# 05_HDMI_to_DP.net
KiCad netlist of a schematic drawn in Altium Designer
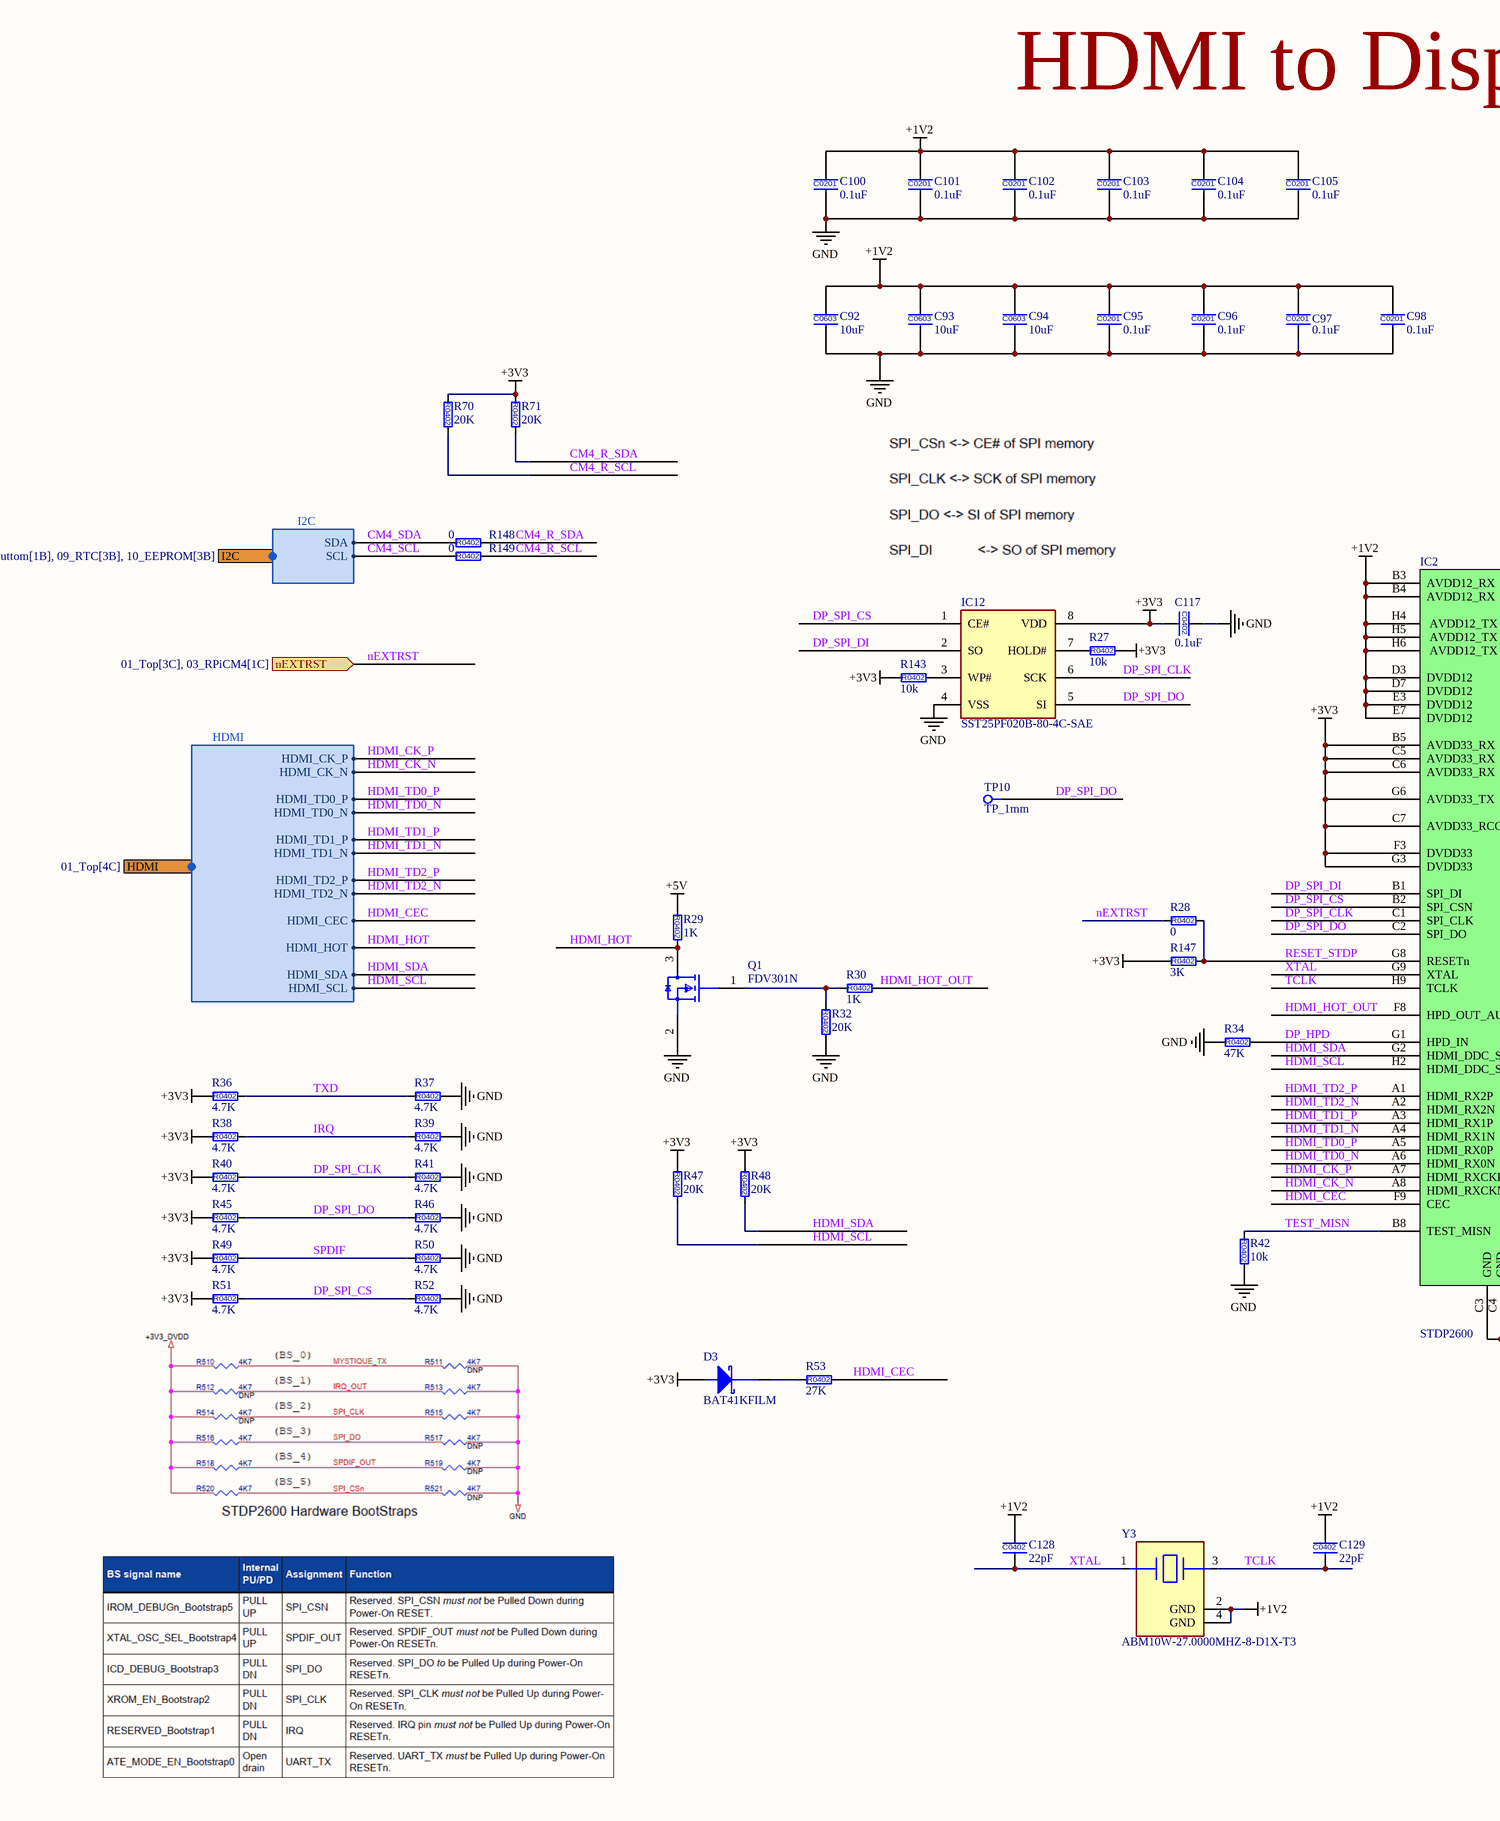
[diagram p0: 05_HDMI_to_DP.SchDoc, left]
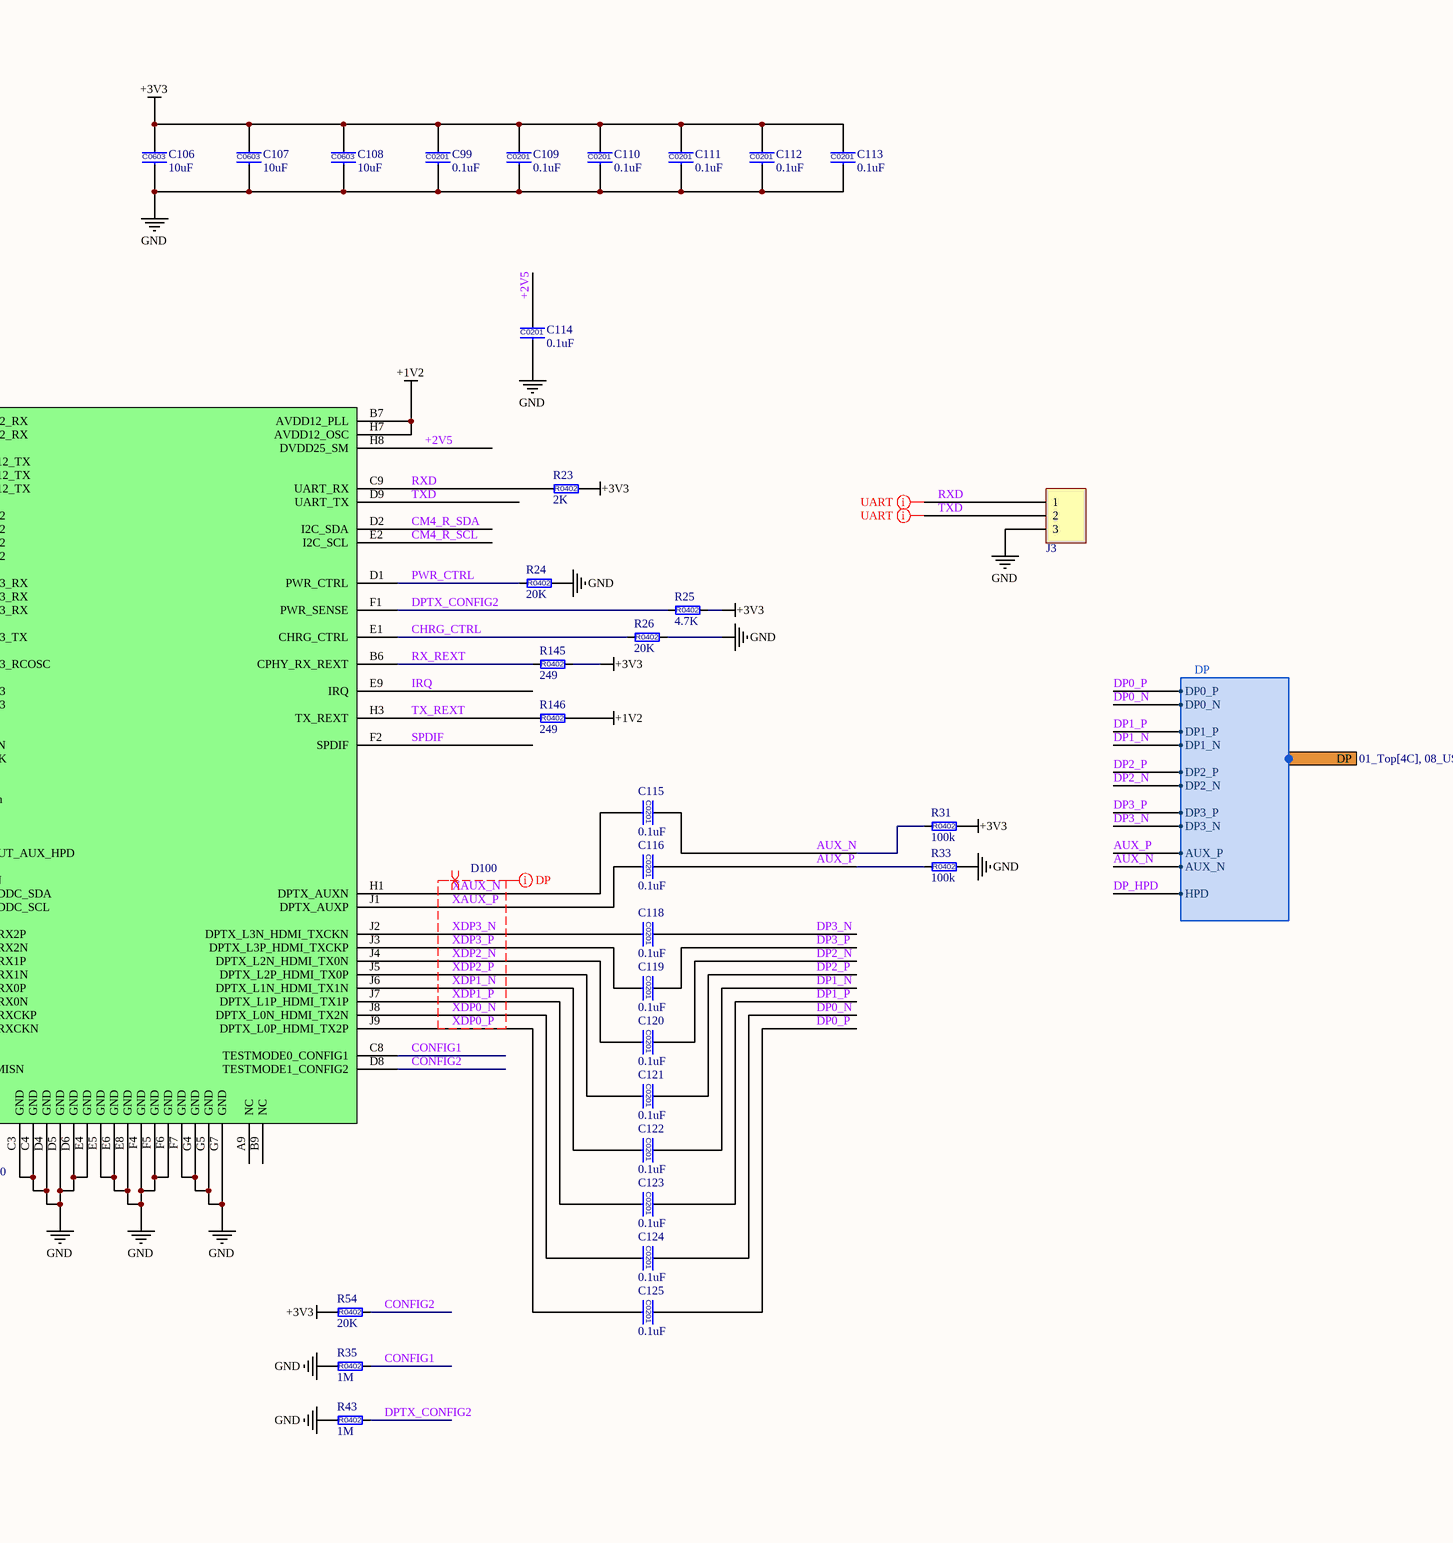
[diagram p1: 05_HDMI_to_DP.SchDoc, right]

(export (version "E")
  (design (tool "Eeschema 10.0.6"))
  (components
    (comp (ref "C92")
      (value "10uF")
      (footprint "C0603")
      (description "CAP CER 10uF 10% 10V X5R 0603")
      (fields
        (field (name "MANUFACTURER") "KYOCERA AVX")
        (field (name "MANUFACTURER PART NUMBER") "0603ZD106KAT2A")
      )
      (libsource (lib "Capacitor") (part "0603ZD106KAT2A"))
    )
    (comp (ref "C93")
      (value "10uF")
      (footprint "C0603")
      (description "CAP CER 10uF 10% 10V X5R 0603")
      (fields
        (field (name "MANUFACTURER") "KYOCERA AVX")
        (field (name "MANUFACTURER PART NUMBER") "0603ZD106KAT2A")
      )
      (libsource (lib "Capacitor") (part "0603ZD106KAT2A"))
    )
    (comp (ref "C94")
      (value "10uF")
      (footprint "C0603")
      (description "CAP CER 10uF 10% 10V X5R 0603")
      (fields
        (field (name "MANUFACTURER") "KYOCERA AVX")
        (field (name "MANUFACTURER PART NUMBER") "0603ZD106KAT2A")
      )
      (libsource (lib "Capacitor") (part "0603ZD106KAT2A"))
    )
    (comp (ref "C95")
      (value "0.1uF")
      (footprint "C0201")
      (description "CAP CER  0.1uF 10% 6.3V X5R 0201")
      (fields
        (field (name "MANUFACTURER") "AVX Corporation")
        (field (name "MANUFACTURER PART NUMBER") "02016D104KAT")
      )
      (libsource (lib "Capacitor") (part "02016D104KAT"))
    )
    (comp (ref "C96")
      (value "0.1uF")
      (footprint "C0201")
      (description "CAP CER  0.1uF 10% 6.3V X5R 0201")
      (fields
        (field (name "MANUFACTURER") "AVX Corporation")
        (field (name "MANUFACTURER PART NUMBER") "02016D104KAT")
      )
      (libsource (lib "Capacitor") (part "02016D104KAT"))
    )
    (comp (ref "C97")
      (value "0.1uF")
      (footprint "C0201")
      (description "CAP CER  0.1uF 10% 6.3V X5R 0201")
      (fields
        (field (name "MANUFACTURER") "AVX Corporation")
        (field (name "MANUFACTURER PART NUMBER") "02016D104KAT")
      )
      (libsource (lib "Capacitor") (part "02016D104KAT"))
    )
    (comp (ref "C98")
      (value "0.1uF")
      (footprint "C0201")
      (description "CAP CER  0.1uF 10% 6.3V X5R 0201")
      (fields
        (field (name "MANUFACTURER") "AVX Corporation")
        (field (name "MANUFACTURER PART NUMBER") "02016D104KAT")
      )
      (libsource (lib "Capacitor") (part "02016D104KAT"))
    )
    (comp (ref "C99")
      (value "0.1uF")
      (footprint "C0201")
      (description "CAP CER  0.1uF 10% 6.3V X5R 0201")
      (fields
        (field (name "MANUFACTURER") "AVX Corporation")
        (field (name "MANUFACTURER PART NUMBER") "02016D104KAT")
      )
      (libsource (lib "Capacitor") (part "02016D104KAT"))
    )
    (comp (ref "C100")
      (value "0.1uF")
      (footprint "C0201")
      (description "CAP CER  0.1uF 10% 6.3V X5R 0201")
      (fields
        (field (name "MANUFACTURER") "AVX Corporation")
        (field (name "MANUFACTURER PART NUMBER") "02016D104KAT")
      )
      (libsource (lib "Capacitor") (part "02016D104KAT"))
    )
    (comp (ref "C101")
      (value "0.1uF")
      (footprint "C0201")
      (description "CAP CER  0.1uF 10% 6.3V X5R 0201")
      (fields
        (field (name "MANUFACTURER") "AVX Corporation")
        (field (name "MANUFACTURER PART NUMBER") "02016D104KAT")
      )
      (libsource (lib "Capacitor") (part "02016D104KAT"))
    )
    (comp (ref "C102")
      (value "0.1uF")
      (footprint "C0201")
      (description "CAP CER  0.1uF 10% 6.3V X5R 0201")
      (fields
        (field (name "MANUFACTURER") "AVX Corporation")
        (field (name "MANUFACTURER PART NUMBER") "02016D104KAT")
      )
      (libsource (lib "Capacitor") (part "02016D104KAT"))
    )
    (comp (ref "C103")
      (value "0.1uF")
      (footprint "C0201")
      (description "CAP CER  0.1uF 10% 6.3V X5R 0201")
      (fields
        (field (name "MANUFACTURER") "AVX Corporation")
        (field (name "MANUFACTURER PART NUMBER") "02016D104KAT")
      )
      (libsource (lib "Capacitor") (part "02016D104KAT"))
    )
    (comp (ref "C104")
      (value "0.1uF")
      (footprint "C0201")
      (description "CAP CER  0.1uF 10% 6.3V X5R 0201")
      (fields
        (field (name "MANUFACTURER") "AVX Corporation")
        (field (name "MANUFACTURER PART NUMBER") "02016D104KAT")
      )
      (libsource (lib "Capacitor") (part "02016D104KAT"))
    )
    (comp (ref "C105")
      (value "0.1uF")
      (footprint "C0201")
      (description "CAP CER  0.1uF 10% 6.3V X5R 0201")
      (fields
        (field (name "MANUFACTURER") "AVX Corporation")
        (field (name "MANUFACTURER PART NUMBER") "02016D104KAT")
      )
      (libsource (lib "Capacitor") (part "02016D104KAT"))
    )
    (comp (ref "C106")
      (value "10uF")
      (footprint "C0603")
      (description "CAP CER 10uF 10% 10V X5R 0603")
      (fields
        (field (name "MANUFACTURER") "KYOCERA AVX")
        (field (name "MANUFACTURER PART NUMBER") "0603ZD106KAT2A")
      )
      (libsource (lib "Capacitor") (part "0603ZD106KAT2A"))
    )
    (comp (ref "C107")
      (value "10uF")
      (footprint "C0603")
      (description "CAP CER 10uF 10% 10V X5R 0603")
      (fields
        (field (name "MANUFACTURER") "KYOCERA AVX")
        (field (name "MANUFACTURER PART NUMBER") "0603ZD106KAT2A")
      )
      (libsource (lib "Capacitor") (part "0603ZD106KAT2A"))
    )
    (comp (ref "C108")
      (value "10uF")
      (footprint "C0603")
      (description "CAP CER 10uF 10% 10V X5R 0603")
      (fields
        (field (name "MANUFACTURER") "KYOCERA AVX")
        (field (name "MANUFACTURER PART NUMBER") "0603ZD106KAT2A")
      )
      (libsource (lib "Capacitor") (part "0603ZD106KAT2A"))
    )
    (comp (ref "C109")
      (value "0.1uF")
      (footprint "C0201")
      (description "CAP CER  0.1uF 10% 6.3V X5R 0201")
      (fields
        (field (name "MANUFACTURER") "AVX Corporation")
        (field (name "MANUFACTURER PART NUMBER") "02016D104KAT")
      )
      (libsource (lib "Capacitor") (part "02016D104KAT"))
    )
    (comp (ref "C110")
      (value "0.1uF")
      (footprint "C0201")
      (description "CAP CER  0.1uF 10% 6.3V X5R 0201")
      (fields
        (field (name "MANUFACTURER") "AVX Corporation")
        (field (name "MANUFACTURER PART NUMBER") "02016D104KAT")
      )
      (libsource (lib "Capacitor") (part "02016D104KAT"))
    )
    (comp (ref "C111")
      (value "0.1uF")
      (footprint "C0201")
      (description "CAP CER  0.1uF 10% 6.3V X5R 0201")
      (fields
        (field (name "MANUFACTURER") "AVX Corporation")
        (field (name "MANUFACTURER PART NUMBER") "02016D104KAT")
      )
      (libsource (lib "Capacitor") (part "02016D104KAT"))
    )
    (comp (ref "C112")
      (value "0.1uF")
      (footprint "C0201")
      (description "CAP CER  0.1uF 10% 6.3V X5R 0201")
      (fields
        (field (name "MANUFACTURER") "AVX Corporation")
        (field (name "MANUFACTURER PART NUMBER") "02016D104KAT")
      )
      (libsource (lib "Capacitor") (part "02016D104KAT"))
    )
    (comp (ref "C113")
      (value "0.1uF")
      (footprint "C0201")
      (description "CAP CER  0.1uF 10% 6.3V X5R 0201")
      (fields
        (field (name "MANUFACTURER") "AVX Corporation")
        (field (name "MANUFACTURER PART NUMBER") "02016D104KAT")
      )
      (libsource (lib "Capacitor") (part "02016D104KAT"))
    )
    (comp (ref "C114")
      (value "0.1uF")
      (footprint "C0201")
      (description "CAP CER  0.1uF 10% 6.3V X5R 0201")
      (fields
        (field (name "MANUFACTURER") "AVX Corporation")
        (field (name "MANUFACTURER PART NUMBER") "02016D104KAT")
      )
      (libsource (lib "Capacitor") (part "02016D104KAT"))
    )
    (comp (ref "C115")
      (value "0.1uF")
      (footprint "C0201")
      (description "CAP CER  0.1uF 10% 6.3V X5R 0201")
      (fields
        (field (name "MANUFACTURER") "AVX Corporation")
        (field (name "MANUFACTURER PART NUMBER") "02016D104KAT")
      )
      (libsource (lib "Capacitor") (part "02016D104KAT"))
    )
    (comp (ref "C116")
      (value "0.1uF")
      (footprint "C0201")
      (description "CAP CER  0.1uF 10% 6.3V X5R 0201")
      (fields
        (field (name "MANUFACTURER") "AVX Corporation")
        (field (name "MANUFACTURER PART NUMBER") "02016D104KAT")
      )
      (libsource (lib "Capacitor") (part "02016D104KAT"))
    )
    (comp (ref "C117")
      (value "0.1uF")
      (footprint "C0402")
      (description "CAP CER  0.1uF 10% 25V X5R 0402")
      (fields
        (field (name "MANUFACTURER") "AVX Corporation")
        (field (name "MANUFACTURER PART NUMBER") "04023D104KAT2A")
      )
      (libsource (lib "Capacitor") (part "04023D104KAT2A"))
    )
    (comp (ref "C118")
      (value "0.1uF")
      (footprint "C0201")
      (description "CAP CER  0.1uF 10% 6.3V X5R 0201")
      (fields
        (field (name "MANUFACTURER") "AVX Corporation")
        (field (name "MANUFACTURER PART NUMBER") "02016D104KAT")
      )
      (libsource (lib "Capacitor") (part "02016D104KAT"))
    )
    (comp (ref "C119")
      (value "0.1uF")
      (footprint "C0201")
      (description "CAP CER  0.1uF 10% 6.3V X5R 0201")
      (fields
        (field (name "MANUFACTURER") "AVX Corporation")
        (field (name "MANUFACTURER PART NUMBER") "02016D104KAT")
      )
      (libsource (lib "Capacitor") (part "02016D104KAT"))
    )
    (comp (ref "C120")
      (value "0.1uF")
      (footprint "C0201")
      (description "CAP CER  0.1uF 10% 6.3V X5R 0201")
      (fields
        (field (name "MANUFACTURER") "AVX Corporation")
        (field (name "MANUFACTURER PART NUMBER") "02016D104KAT")
      )
      (libsource (lib "Capacitor") (part "02016D104KAT"))
    )
    (comp (ref "C121")
      (value "0.1uF")
      (footprint "C0201")
      (description "CAP CER  0.1uF 10% 6.3V X5R 0201")
      (fields
        (field (name "MANUFACTURER") "AVX Corporation")
        (field (name "MANUFACTURER PART NUMBER") "02016D104KAT")
      )
      (libsource (lib "Capacitor") (part "02016D104KAT"))
    )
    (comp (ref "C122")
      (value "0.1uF")
      (footprint "C0201")
      (description "CAP CER  0.1uF 10% 6.3V X5R 0201")
      (fields
        (field (name "MANUFACTURER") "AVX Corporation")
        (field (name "MANUFACTURER PART NUMBER") "02016D104KAT")
      )
      (libsource (lib "Capacitor") (part "02016D104KAT"))
    )
    (comp (ref "C123")
      (value "0.1uF")
      (footprint "C0201")
      (description "CAP CER  0.1uF 10% 6.3V X5R 0201")
      (fields
        (field (name "MANUFACTURER") "AVX Corporation")
        (field (name "MANUFACTURER PART NUMBER") "02016D104KAT")
      )
      (libsource (lib "Capacitor") (part "02016D104KAT"))
    )
    (comp (ref "C124")
      (value "0.1uF")
      (footprint "C0201")
      (description "CAP CER  0.1uF 10% 6.3V X5R 0201")
      (fields
        (field (name "MANUFACTURER") "AVX Corporation")
        (field (name "MANUFACTURER PART NUMBER") "02016D104KAT")
      )
      (libsource (lib "Capacitor") (part "02016D104KAT"))
    )
    (comp (ref "C125")
      (value "0.1uF")
      (footprint "C0201")
      (description "CAP CER  0.1uF 10% 6.3V X5R 0201")
      (fields
        (field (name "MANUFACTURER") "AVX Corporation")
        (field (name "MANUFACTURER PART NUMBER") "02016D104KAT")
      )
      (libsource (lib "Capacitor") (part "02016D104KAT"))
    )
    (comp (ref "C128")
      (value "22pF")
      (footprint "C0402")
      (description "CAP CER 22pF 10% 25V NP0 0402")
      (fields
        (field (name "MANUFACTURER") "KYOCERA AVX")
        (field (name "MANUFACTURER PART NUMBER") "04023A220KAT2A")
      )
      (libsource (lib "Capacitor") (part "04023A220KAT2A"))
    )
    (comp (ref "C129")
      (value "22pF")
      (footprint "C0402")
      (description "CAP CER 22pF 10% 25V NP0 0402")
      (fields
        (field (name "MANUFACTURER") "KYOCERA AVX")
        (field (name "MANUFACTURER PART NUMBER") "04023A220KAT2A")
      )
      (libsource (lib "Capacitor") (part "04023A220KAT2A"))
    )
    (comp (ref "D3")
      (value "BAT41KFILM")
      (footprint "BAT41KFILM_SOD-523-2")
      (description "DIODE SCHOTTKY 100V 200MA SOD523")
      (fields
        (field (name "OCTOPART") "https://octopart.com/bat41kfilm-stmicroelectronics-658186")
        (field (name "MANUFACTURER") "STMicroelectronics")
      )
      (libsource (lib "new") (part "BAT41KFILM"))
    )
    (comp (ref "IC2")
      (value "STDP2600")
      (footprint "STDP2600_BGA-81")
      (description "Advanced HDMI to DisplayPort converter")
      (fields (field (name "PART NUMBER") "IC0077") (field (name "MANUFACTURER") "Kinetic Technologies"))
      (libsource (lib "new") (part "STDP2600"))
    )
    (comp (ref "IC12")
      (value "SST25PF020B-80-4C-SAE")
      (footprint "SST25PF020B-80-4C-SAE_SOIC_8")
      (description "150 mils SOIC 2.3-3.6V 2 Mbit SPI Flash 8 SOIC 3.90mm(.150in) TUBE RoHS Compliant: Yes")
      (fields
        (field (name "MOUSER PART NUMBER") "579-020B-80-4C-SAE")
        (field (name "MANUFACTURER") "Microchip")
      )
      (libsource (lib "new") (part "SST25PF020B-80-4C-SAE"))
    )
    (comp (ref "J3")
      (value "PLS-3")
      (footprint "PLS-3-3D")
      (description "Board to Board Connector Straight Header Single Row 3 Position 2.54mm Pitch Through Hole Bag")
      (fields
        (field (name "MANUFACTURER") "Amphenol")
        (field (name "MANUFACTURER PART NUMBER") "G800W305018EU")
      )
      (libsource (lib "Connector") (part "PLS-3"))
    )
    (comp (ref "Q1")
      (value "FDV301N")
      (footprint "FDV301N_SOT_23")
      (description "MOSFET N-CH 25V 220MA SOT-23")
      (fields
        (field (name "MANUFACTURER") "ON Semiconductor")
        (field (name "OCTOPART") "https://octopart.com/fdv301n-on+semiconductor-84326713")
      )
      (libsource (lib "new") (part "FDV301N"))
    )
    (comp (ref "R23")
      (value "2K")
      (footprint "R0402")
      (description "RES SMD 2K ohm 1% 1/16W R0402")
      (fields
        (field (name "MANUFACTURER") "Vishay")
        (field (name "MANUFACTURER PART NUMBER") "CRCW04022K00FKEE")
      )
      (libsource (lib "Resistor") (part "CRCW04022K00FKEE"))
    )
    (comp (ref "R24")
      (value "20K")
      (footprint "R0402")
      (description "RES SMD 20K ohm 1% 1/16W R0402")
      (fields
        (field (name "MANUFACTURER") "Vishay Dale")
        (field (name "MANUFACTURER PART NUMBER") "CRCW040220K0FK")
      )
      (libsource (lib "Resistor") (part "CRCW040220K0FK"))
    )
    (comp (ref "R25")
      (value "4.7K")
      (footprint "R0402")
      (description "RES SMD 4.7K ohm 1% 1/16W R0402")
      (fields
        (field (name "MANUFACTURER") "Vishay Dale")
        (field (name "MANUFACTURER PART NUMBER") "CRCW04024K7FK")
      )
      (libsource (lib "Resistor") (part "CRCW04024K7FK"))
    )
    (comp (ref "R26")
      (value "20K")
      (footprint "R0402")
      (description "RES SMD 20K ohm 1% 1/16W R0402")
      (fields
        (field (name "MANUFACTURER") "Vishay Dale")
        (field (name "MANUFACTURER PART NUMBER") "CRCW040220K0FK")
      )
      (libsource (lib "Resistor") (part "CRCW040220K0FK"))
    )
    (comp (ref "R27")
      (value "10k")
      (footprint "R0402")
      (description "RES SMD 10K ohm 1% 1/16W R0402")
      (fields
        (field (name "MANUFACTURER") "Vishay Dale")
        (field (name "MANUFACTURER PART NUMBER") "CRCW040210K0FK")
      )
      (libsource (lib "Resistor") (part "CRCW040210K0FK"))
    )
    (comp (ref "R28")
      (value "0")
      (footprint "R0402")
      (description "RES SMD 0 ohm 1/16W R0402")
      (fields
        (field (name "MANUFACTURER") "Vishay Dale")
        (field (name "MANUFACTURER PART NUMBER") "CRCW04020000Z0")
      )
      (libsource (lib "Resistor") (part "CRCW04020000Z0"))
    )
    (comp (ref "R29")
      (value "1K")
      (footprint "R0402")
      (description "RES SMD 1K ohm 1% 1/16W R0402")
      (fields
        (field (name "MANUFACTURER") "Vishay Dale")
        (field (name "MANUFACTURER PART NUMBER") "CRCW04021K00FK")
      )
      (libsource (lib "Resistor") (part "CRCW04021K00FK"))
    )
    (comp (ref "R30")
      (value "1K")
      (footprint "R0402")
      (description "RES SMD 1K ohm 1% 1/16W R0402")
      (fields
        (field (name "MANUFACTURER") "Vishay Dale")
        (field (name "MANUFACTURER PART NUMBER") "CRCW04021K00FK")
      )
      (libsource (lib "Resistor") (part "CRCW04021K00FK"))
    )
    (comp (ref "R31")
      (value "100k")
      (footprint "R0402")
      (description "RES SMD 100K ohm 1% 1/16W R0402")
      (fields
        (field (name "MANUFACTURER") "Vishay Dale")
        (field (name "MANUFACTURER PART NUMBER") "CRCW0402100KFK")
      )
      (libsource (lib "Resistor") (part "CRCW0402100KFK"))
    )
    (comp (ref "R32")
      (value "20K")
      (footprint "R0402")
      (description "RES SMD 20K ohm 1% 1/16W R0402")
      (fields
        (field (name "MANUFACTURER") "Vishay Dale")
        (field (name "MANUFACTURER PART NUMBER") "CRCW040220K0FK")
      )
      (libsource (lib "Resistor") (part "CRCW040220K0FK"))
    )
    (comp (ref "R33")
      (value "100k")
      (footprint "R0402")
      (description "RES SMD 100K ohm 1% 1/16W R0402")
      (fields
        (field (name "MANUFACTURER") "Vishay Dale")
        (field (name "MANUFACTURER PART NUMBER") "CRCW0402100KFK")
      )
      (libsource (lib "Resistor") (part "CRCW0402100KFK"))
    )
    (comp (ref "R34")
      (value "47K")
      (footprint "R0402")
      (description "RES SMD 47K ohm 1% 1/16W R0402")
      (fields
        (field (name "MANUFACTURER") "Vishay Dale")
        (field (name "MANUFACTURER PART NUMBER") "CRCW040247K0FK")
      )
      (libsource (lib "Resistor") (part "CRCW040247K0FK"))
    )
    (comp (ref "R35")
      (value "1M")
      (footprint "R0402")
      (description "RES SMD 1M ohm 1% 1/16W R0402")
      (fields
        (field (name "MANUFACTURER") "Vishay")
        (field (name "MANUFACTURER PART NUMBER") "CRCW04021M00FKEDC")
      )
      (libsource (lib "Resistor") (part "CRCW04021M00FKEDC"))
    )
    (comp (ref "R36")
      (value "4.7K")
      (footprint "R0402")
      (description "RES SMD 4.7K ohm 1% 1/16W R0402")
      (fields
        (field (name "MANUFACTURER") "Vishay Dale")
        (field (name "MANUFACTURER PART NUMBER") "CRCW04024K7FK")
      )
      (libsource (lib "Resistor") (part "CRCW04024K7FK"))
    )
    (comp (ref "R37")
      (value "4.7K")
      (footprint "R0402")
      (description "RES SMD 4.7K ohm 1% 1/16W R0402")
      (fields
        (field (name "MANUFACTURER") "Vishay Dale")
        (field (name "MANUFACTURER PART NUMBER") "CRCW04024K7FK")
      )
      (libsource (lib "Resistor") (part "CRCW04024K7FK"))
    )
    (comp (ref "R38")
      (value "4.7K")
      (footprint "R0402")
      (description "RES SMD 4.7K ohm 1% 1/16W R0402")
      (fields
        (field (name "MANUFACTURER") "Vishay Dale")
        (field (name "MANUFACTURER PART NUMBER") "CRCW04024K7FK")
      )
      (libsource (lib "Resistor") (part "CRCW04024K7FK"))
    )
    (comp (ref "R39")
      (value "4.7K")
      (footprint "R0402")
      (description "RES SMD 4.7K ohm 1% 1/16W R0402")
      (fields
        (field (name "MANUFACTURER") "Vishay Dale")
        (field (name "MANUFACTURER PART NUMBER") "CRCW04024K7FK")
      )
      (libsource (lib "Resistor") (part "CRCW04024K7FK"))
    )
    (comp (ref "R40")
      (value "4.7K")
      (footprint "R0402")
      (description "RES SMD 4.7K ohm 1% 1/16W R0402")
      (fields
        (field (name "MANUFACTURER") "Vishay Dale")
        (field (name "MANUFACTURER PART NUMBER") "CRCW04024K7FK")
      )
      (libsource (lib "Resistor") (part "CRCW04024K7FK"))
    )
    (comp (ref "R41")
      (value "4.7K")
      (footprint "R0402")
      (description "RES SMD 4.7K ohm 1% 1/16W R0402")
      (fields
        (field (name "MANUFACTURER") "Vishay Dale")
        (field (name "MANUFACTURER PART NUMBER") "CRCW04024K7FK")
      )
      (libsource (lib "Resistor") (part "CRCW04024K7FK"))
    )
    (comp (ref "R42")
      (value "10k")
      (footprint "R0402")
      (description "RES SMD 10K ohm 1% 1/16W R0402")
      (fields
        (field (name "MANUFACTURER") "Vishay Dale")
        (field (name "MANUFACTURER PART NUMBER") "CRCW040210K0FK")
      )
      (libsource (lib "Resistor") (part "CRCW040210K0FK"))
    )
    (comp (ref "R43")
      (value "1M")
      (footprint "R0402")
      (description "RES SMD 1M ohm 1% 1/16W R0402")
      (fields
        (field (name "MANUFACTURER") "Vishay")
        (field (name "MANUFACTURER PART NUMBER") "CRCW04021M00FKEDC")
      )
      (libsource (lib "Resistor") (part "CRCW04021M00FKEDC"))
    )
    (comp (ref "R45")
      (value "4.7K")
      (footprint "R0402")
      (description "RES SMD 4.7K ohm 1% 1/16W R0402")
      (fields
        (field (name "MANUFACTURER") "Vishay Dale")
        (field (name "MANUFACTURER PART NUMBER") "CRCW04024K7FK")
      )
      (libsource (lib "Resistor") (part "CRCW04024K7FK"))
    )
    (comp (ref "R46")
      (value "4.7K")
      (footprint "R0402")
      (description "RES SMD 4.7K ohm 1% 1/16W R0402")
      (fields
        (field (name "MANUFACTURER") "Vishay Dale")
        (field (name "MANUFACTURER PART NUMBER") "CRCW04024K7FK")
      )
      (libsource (lib "Resistor") (part "CRCW04024K7FK"))
    )
    (comp (ref "R47")
      (value "20K")
      (footprint "R0402")
      (description "RES SMD 20K ohm 1% 1/16W R0402")
      (fields
        (field (name "MANUFACTURER") "Vishay Dale")
        (field (name "MANUFACTURER PART NUMBER") "CRCW040220K0FK")
      )
      (libsource (lib "Resistor") (part "CRCW040220K0FK"))
    )
    (comp (ref "R48")
      (value "20K")
      (footprint "R0402")
      (description "RES SMD 20K ohm 1% 1/16W R0402")
      (fields
        (field (name "MANUFACTURER") "Vishay Dale")
        (field (name "MANUFACTURER PART NUMBER") "CRCW040220K0FK")
      )
      (libsource (lib "Resistor") (part "CRCW040220K0FK"))
    )
    (comp (ref "R49")
      (value "4.7K")
      (footprint "R0402")
      (description "RES SMD 4.7K ohm 1% 1/16W R0402")
      (fields
        (field (name "MANUFACTURER") "Vishay Dale")
        (field (name "MANUFACTURER PART NUMBER") "CRCW04024K7FK")
      )
      (libsource (lib "Resistor") (part "CRCW04024K7FK"))
    )
    (comp (ref "R50")
      (value "4.7K")
      (footprint "R0402")
      (description "RES SMD 4.7K ohm 1% 1/16W R0402")
      (fields
        (field (name "MANUFACTURER") "Vishay Dale")
        (field (name "MANUFACTURER PART NUMBER") "CRCW04024K7FK")
      )
      (libsource (lib "Resistor") (part "CRCW04024K7FK"))
    )
    (comp (ref "R51")
      (value "4.7K")
      (footprint "R0402")
      (description "RES SMD 4.7K ohm 1% 1/16W R0402")
      (fields
        (field (name "MANUFACTURER") "Vishay Dale")
        (field (name "MANUFACTURER PART NUMBER") "CRCW04024K7FK")
      )
      (libsource (lib "Resistor") (part "CRCW04024K7FK"))
    )
    (comp (ref "R52")
      (value "4.7K")
      (footprint "R0402")
      (description "RES SMD 4.7K ohm 1% 1/16W R0402")
      (fields
        (field (name "MANUFACTURER") "Vishay Dale")
        (field (name "MANUFACTURER PART NUMBER") "CRCW04024K7FK")
      )
      (libsource (lib "Resistor") (part "CRCW04024K7FK"))
    )
    (comp (ref "R53")
      (value "27K")
      (footprint "R0402")
      (description "RES SMD 27K ohm 1% 1/16W R0402")
      (fields
        (field (name "MANUFACTURER") "Vishay Dale")
        (field (name "MANUFACTURER PART NUMBER") "CRCW040227K0FK")
      )
      (libsource (lib "Resistor") (part "CRCW040227K0FK"))
    )
    (comp (ref "R54")
      (value "20K")
      (footprint "R0402")
      (description "RES SMD 20K ohm 1% 1/16W R0402")
      (fields
        (field (name "MANUFACTURER") "Vishay Dale")
        (field (name "MANUFACTURER PART NUMBER") "CRCW040220K0FK")
      )
      (libsource (lib "Resistor") (part "CRCW040220K0FK"))
    )
    (comp (ref "R70")
      (value "20K")
      (footprint "R0402")
      (description "RES SMD 20K ohm 1% 1/16W R0402")
      (fields
        (field (name "MANUFACTURER") "Vishay Dale")
        (field (name "MANUFACTURER PART NUMBER") "CRCW040220K0FK")
      )
      (libsource (lib "Resistor") (part "CRCW040220K0FK"))
    )
    (comp (ref "R71")
      (value "20K")
      (footprint "R0402")
      (description "RES SMD 20K ohm 1% 1/16W R0402")
      (fields
        (field (name "MANUFACTURER") "Vishay Dale")
        (field (name "MANUFACTURER PART NUMBER") "CRCW040220K0FK")
      )
      (libsource (lib "Resistor") (part "CRCW040220K0FK"))
    )
    (comp (ref "R143")
      (value "10k")
      (footprint "R0402")
      (description "RES SMD 10K ohm 1% 1/16W R0402")
      (fields
        (field (name "MANUFACTURER") "Vishay Dale")
        (field (name "MANUFACTURER PART NUMBER") "CRCW040210K0FK")
      )
      (libsource (lib "Resistor") (part "CRCW040210K0FK"))
    )
    (comp (ref "R145")
      (value "249")
      (footprint "R0402")
      (description "RES SMD 249 ohm 1% 1/16W R0402")
      (fields
        (field (name "MANUFACTURER") "Vishay")
        (field (name "MANUFACTURER PART NUMBER") "CRCW0402249RFKEDC")
      )
      (libsource (lib "Resistor") (part "CRCW0402249RFKEDC"))
    )
    (comp (ref "R146")
      (value "249")
      (footprint "R0402")
      (description "RES SMD 249 ohm 1% 1/16W R0402")
      (fields
        (field (name "MANUFACTURER") "Vishay")
        (field (name "MANUFACTURER PART NUMBER") "CRCW0402249RFKEDC")
      )
      (libsource (lib "Resistor") (part "CRCW0402249RFKEDC"))
    )
    (comp (ref "R147")
      (value "3K")
      (footprint "R0402")
      (description "RES SMD 3K ohm 1% 1/16W R0402")
      (fields
        (field (name "MANUFACTURER") "Vishay")
        (field (name "MANUFACTURER PART NUMBER") "CRCW04023K00FKED")
      )
      (libsource (lib "Resistor") (part "CRCW04023K00FKED"))
    )
    (comp (ref "R148")
      (value "0")
      (footprint "R0402")
      (description "RES SMD 0 ohm 1/16W R0402")
      (fields
        (field (name "MANUFACTURER") "Vishay Dale")
        (field (name "MANUFACTURER PART NUMBER") "CRCW04020000Z0")
      )
      (libsource (lib "Resistor") (part "CRCW04020000Z0"))
    )
    (comp (ref "R149")
      (value "0")
      (footprint "R0402")
      (description "RES SMD 0 ohm 1/16W R0402")
      (fields
        (field (name "MANUFACTURER") "Vishay Dale")
        (field (name "MANUFACTURER PART NUMBER") "CRCW04020000Z0")
      )
      (libsource (lib "Resistor") (part "CRCW04020000Z0"))
    )
    (comp (ref "TP10")
      (value "TP_1mm")
      (footprint "TP_1MM")
      (description "Testpoint 1mm")
      (fields (field (name "MANUFACTURER PART NUMBER") "General Test Point"))
      (libsource (lib "test_point_solder_bridge") (part "TP_1mm"))
    )
    (comp (ref "Y3")
      (value "ABM10W-27.0000MHZ-8-D1X-T3")
      (footprint "ABM10W")
      (description "CRYSTAL 27.0000MHZ 8PF SMD, 2.5x2mm, RoHS")
      (fields (field (name "MANUFACTURER") "Abracon"))
      (libsource (lib "new") (part "ABM10W-27.0000MHZ-8-D1X-T3"))
    )
  )
  (nets
    (net (code "4") (name "+1V2") (class "Default")
      (node (ref "C100") (pin "1") (pinfunction "1_1") (pintype "passive"))
      (node (ref "C101") (pin "1") (pinfunction "1_1") (pintype "passive"))
      (node (ref "C102") (pin "1") (pinfunction "1_1") (pintype "passive"))
      (node (ref "C103") (pin "1") (pinfunction "1_1") (pintype "passive"))
      (node (ref "C104") (pin "1") (pinfunction "1_1") (pintype "passive"))
      (node (ref "C105") (pin "1") (pinfunction "1_1") (pintype "passive"))
      (node (ref "C128") (pin "1") (pinfunction "1_1") (pintype "passive"))
      (node (ref "C129") (pin "1") (pinfunction "1_1") (pintype "passive"))
      (node (ref "C92") (pin "1") (pinfunction "1_1") (pintype "passive"))
      (node (ref "C93") (pin "1") (pinfunction "1_1") (pintype "passive"))
      (node (ref "C94") (pin "1") (pinfunction "1_1") (pintype "passive"))
      (node (ref "C95") (pin "1") (pinfunction "1_1") (pintype "passive"))
      (node (ref "C96") (pin "1") (pinfunction "1_1") (pintype "passive"))
      (node (ref "C97") (pin "1") (pinfunction "1_1") (pintype "passive"))
      (node (ref "C98") (pin "1") (pinfunction "1_1") (pintype "passive"))
      (node (ref "IC2") (pin "B3") (pinfunction "AVDD12_RX_B3") (pintype "passive"))
      (node (ref "IC2") (pin "B4") (pinfunction "AVDD12_RX_B4") (pintype "passive"))
      (node (ref "IC2") (pin "B7") (pinfunction "AVDD12_PLL_B7") (pintype "passive"))
      (node (ref "IC2") (pin "D3") (pinfunction "DVDD12_D3") (pintype "passive"))
      (node (ref "IC2") (pin "D7") (pinfunction "DVDD12_D7") (pintype "passive"))
      (node (ref "IC2") (pin "E3") (pinfunction "DVDD12_E3") (pintype "passive"))
      (node (ref "IC2") (pin "E7") (pinfunction "DVDD12_E7") (pintype "passive"))
      (node (ref "IC2") (pin "H4") (pinfunction "_AVDD12_TX_H4") (pintype "passive"))
      (node (ref "IC2") (pin "H5") (pinfunction "_AVDD12_TX_H5") (pintype "passive"))
      (node (ref "IC2") (pin "H6") (pinfunction "_AVDD12_TX_H6") (pintype "passive"))
      (node (ref "IC2") (pin "H7") (pinfunction "AVDD12_OSC_H7") (pintype "passive"))
      (node (ref "R146") (pin "2") (pinfunction "2_2") (pintype "passive"))
      (node (ref "Y3") (pin "2") (pinfunction "GND_2") (pintype "power_in"))
      (node (ref "Y3") (pin "4") (pinfunction "GND_4") (pintype "power_in"))
    )
    (net (code "5") (name "+3V3") (class "Default")
      (node (ref "C106") (pin "1") (pinfunction "1_1") (pintype "passive"))
      (node (ref "C107") (pin "1") (pinfunction "1_1") (pintype "passive"))
      (node (ref "C108") (pin "1") (pinfunction "1_1") (pintype "passive"))
      (node (ref "C109") (pin "1") (pinfunction "1_1") (pintype "passive"))
      (node (ref "C110") (pin "1") (pinfunction "1_1") (pintype "passive"))
      (node (ref "C111") (pin "1") (pinfunction "1_1") (pintype "passive"))
      (node (ref "C112") (pin "1") (pinfunction "1_1") (pintype "passive"))
      (node (ref "C113") (pin "1") (pinfunction "1_1") (pintype "passive"))
      (node (ref "C117") (pin "2") (pinfunction "2_2") (pintype "passive"))
      (node (ref "C99") (pin "1") (pinfunction "1_1") (pintype "passive"))
      (node (ref "D3") (pin "2") (pinfunction "Anode_2") (pintype "passive"))
      (node (ref "IC12") (pin "8") (pinfunction "VDD_8") (pintype "passive"))
      (node (ref "IC2") (pin "B5") (pinfunction "AVDD33_RX_B5") (pintype "passive"))
      (node (ref "IC2") (pin "C5") (pinfunction "AVDD33_RX_C5") (pintype "passive"))
      (node (ref "IC2") (pin "C6") (pinfunction "AVDD33_RX_C6") (pintype "passive"))
      (node (ref "IC2") (pin "C7") (pinfunction "AVDD33_RCOSC_C7") (pintype "passive"))
      (node (ref "IC2") (pin "F3") (pinfunction "DVDD33_F3") (pintype "passive"))
      (node (ref "IC2") (pin "G3") (pinfunction "DVDD33_G3") (pintype "passive"))
      (node (ref "IC2") (pin "G6") (pinfunction "AVDD33_TX_G6") (pintype "passive"))
      (node (ref "R143") (pin "1") (pinfunction "1_1") (pintype "passive"))
      (node (ref "R145") (pin "2") (pinfunction "2_2") (pintype "passive"))
      (node (ref "R147") (pin "1") (pinfunction "1_1") (pintype "passive"))
      (node (ref "R23") (pin "2") (pinfunction "2_2") (pintype "passive"))
      (node (ref "R25") (pin "2") (pinfunction "2_2") (pintype "passive"))
      (node (ref "R27") (pin "2") (pinfunction "2_2") (pintype "passive"))
      (node (ref "R31") (pin "2") (pinfunction "2_2") (pintype "passive"))
      (node (ref "R36") (pin "1") (pinfunction "1_1") (pintype "passive"))
      (node (ref "R38") (pin "1") (pinfunction "1_1") (pintype "passive"))
      (node (ref "R40") (pin "1") (pinfunction "1_1") (pintype "passive"))
      (node (ref "R45") (pin "1") (pinfunction "1_1") (pintype "passive"))
      (node (ref "R47") (pin "1") (pinfunction "1_1") (pintype "passive"))
      (node (ref "R48") (pin "1") (pinfunction "1_1") (pintype "passive"))
      (node (ref "R49") (pin "1") (pinfunction "1_1") (pintype "passive"))
      (node (ref "R51") (pin "1") (pinfunction "1_1") (pintype "passive"))
      (node (ref "R54") (pin "1") (pinfunction "1_1") (pintype "passive"))
      (node (ref "R70") (pin "1") (pinfunction "1_1") (pintype "passive"))
      (node (ref "R71") (pin "1") (pinfunction "1_1") (pintype "passive"))
    )
    (net (code "6") (name "+5V") (class "Default")
      (node (ref "R29") (pin "1") (pinfunction "1_1") (pintype "passive"))
    )
    (net (code "7") (name "/+2V5") (class "Default")
      (node (ref "C114") (pin "1") (pinfunction "1_1") (pintype "passive"))
      (node (ref "IC2") (pin "H8") (pinfunction "DVDD25_SM_H8") (pintype "passive"))
    )
    (net (code "8") (name "/AUX_N") (class "Default")
      (node (ref "C115") (pin "1") (pinfunction "1_1") (pintype "passive"))
      (node (ref "R31") (pin "1") (pinfunction "1_1") (pintype "passive"))
    )
    (net (code "9") (name "/AUX_P") (class "Default")
      (node (ref "C116") (pin "1") (pinfunction "1_1") (pintype "passive"))
      (node (ref "R33") (pin "1") (pinfunction "1_1") (pintype "passive"))
    )
    (net (code "10") (name "/CHRG_CTRL") (class "Default")
      (node (ref "IC2") (pin "E1") (pinfunction "CHRG_CTRL_E1") (pintype "passive"))
      (node (ref "R26") (pin "1") (pinfunction "1_1") (pintype "passive"))
    )
    (net (code "11") (name "/CM4_R_SCL") (class "Default")
      (node (ref "IC2") (pin "E2") (pinfunction "I2C_SCL_E2") (pintype "passive"))
      (node (ref "R149") (pin "2") (pinfunction "2_2") (pintype "passive"))
      (node (ref "R70") (pin "2") (pinfunction "2_2") (pintype "passive"))
    )
    (net (code "12") (name "/CM4_R_SDA") (class "Default")
      (node (ref "IC2") (pin "D2") (pinfunction "I2C_SDA_D2") (pintype "passive"))
      (node (ref "R148") (pin "2") (pinfunction "2_2") (pintype "passive"))
      (node (ref "R71") (pin "2") (pinfunction "2_2") (pintype "passive"))
    )
    (net (code "13") (name "/CM4_SCL") (class "Default")
      (node (ref "R149") (pin "1") (pinfunction "1_1") (pintype "passive"))
    )
    (net (code "14") (name "/CM4_SDA") (class "Default")
      (node (ref "R148") (pin "1") (pinfunction "1_1") (pintype "passive"))
    )
    (net (code "15") (name "/CONFIG1") (class "Default")
      (node (ref "IC2") (pin "C8") (pinfunction "TESTMODE0_CONFIG1_C8") (pintype "passive"))
      (node (ref "R35") (pin "2") (pinfunction "2_2") (pintype "passive"))
    )
    (net (code "16") (name "/CONFIG2") (class "Default")
      (node (ref "IC2") (pin "D8") (pinfunction "TESTMODE1_CONFIG2_D8") (pintype "passive"))
      (node (ref "R54") (pin "2") (pinfunction "2_2") (pintype "passive"))
    )
    (net (code "17") (name "/DP0_N") (class "Default")
      (node (ref "C124") (pin "1") (pinfunction "1_1") (pintype "passive"))
    )
    (net (code "18") (name "/DP0_P") (class "Default")
      (node (ref "C125") (pin "1") (pinfunction "1_1") (pintype "passive"))
    )
    (net (code "19") (name "/DP1_N") (class "Default")
      (node (ref "C122") (pin "1") (pinfunction "1_1") (pintype "passive"))
    )
    (net (code "20") (name "/DP1_P") (class "Default")
      (node (ref "C123") (pin "1") (pinfunction "1_1") (pintype "passive"))
    )
    (net (code "21") (name "/DP2_N") (class "Default")
      (node (ref "C120") (pin "1") (pinfunction "1_1") (pintype "passive"))
    )
    (net (code "22") (name "/DP2_P") (class "Default")
      (node (ref "C121") (pin "1") (pinfunction "1_1") (pintype "passive"))
    )
    (net (code "23") (name "/DP3_N") (class "Default")
      (node (ref "C118") (pin "1") (pinfunction "1_1") (pintype "passive"))
    )
    (net (code "24") (name "/DP3_P") (class "Default")
      (node (ref "C119") (pin "1") (pinfunction "1_1") (pintype "passive"))
    )
    (net (code "25") (name "/DPTX_CONFIG2") (class "Default")
      (node (ref "IC2") (pin "F1") (pinfunction "PWR_SENSE_F1") (pintype "passive"))
      (node (ref "R25") (pin "1") (pinfunction "1_1") (pintype "passive"))
      (node (ref "R43") (pin "2") (pinfunction "2_2") (pintype "passive"))
    )
    (net (code "26") (name "/DP_HPD") (class "Default")
      (node (ref "IC2") (pin "G1") (pinfunction "HPD_IN_G1") (pintype "passive"))
      (node (ref "R34") (pin "2") (pinfunction "2_2") (pintype "passive"))
    )
    (net (code "27") (name "/DP_SPI_CLK") (class "Default")
      (node (ref "IC12") (pin "6") (pinfunction "SCK_6") (pintype "passive"))
      (node (ref "IC2") (pin "C1") (pinfunction "SPI_CLK_C1") (pintype "passive"))
      (node (ref "R40") (pin "2") (pinfunction "2_2") (pintype "passive"))
      (node (ref "R41") (pin "1") (pinfunction "1_1") (pintype "passive"))
    )
    (net (code "28") (name "/DP_SPI_CS") (class "Default")
      (node (ref "IC12") (pin "1") (pinfunction "CE#_1") (pintype "passive"))
      (node (ref "IC2") (pin "B2") (pinfunction "SPI_CSN_B2") (pintype "passive"))
      (node (ref "R51") (pin "2") (pinfunction "2_2") (pintype "passive"))
      (node (ref "R52") (pin "1") (pinfunction "1_1") (pintype "passive"))
    )
    (net (code "29") (name "/DP_SPI_DI") (class "Default")
      (node (ref "IC12") (pin "2") (pinfunction "SO_2") (pintype "passive"))
      (node (ref "IC2") (pin "B1") (pinfunction "SPI_DI_B1") (pintype "passive"))
    )
    (net (code "30") (name "/DP_SPI_DO") (class "Default")
      (node (ref "IC12") (pin "5") (pinfunction "SI_5") (pintype "passive"))
      (node (ref "IC2") (pin "C2") (pinfunction "SPI_DO_C2") (pintype "passive"))
      (node (ref "R45") (pin "2") (pinfunction "2_2") (pintype "passive"))
      (node (ref "R46") (pin "1") (pinfunction "1_1") (pintype "passive"))
      (node (ref "TP10") (pin "1") (pinfunction "1_1") (pintype "passive"))
    )
    (net (code "31") (name "/HDMI_CEC") (class "Default")
      (node (ref "IC2") (pin "F9") (pinfunction "CEC_F9") (pintype "passive"))
      (node (ref "R53") (pin "2") (pinfunction "2_2") (pintype "passive"))
    )
    (net (code "32") (name "/HDMI_CK_N") (class "Default")
      (node (ref "IC2") (pin "A8") (pinfunction "HDMI_RXCKN_A8") (pintype "passive"))
    )
    (net (code "33") (name "/HDMI_CK_P") (class "Default")
      (node (ref "IC2") (pin "A7") (pinfunction "HDMI_RXCKP_A7") (pintype "passive"))
    )
    (net (code "34") (name "/HDMI_HOT") (class "Default")
      (node (ref "Q1") (pin "3") (pinfunction "D_3") (pintype "passive"))
      (node (ref "R29") (pin "2") (pinfunction "2_2") (pintype "passive"))
    )
    (net (code "35") (name "/HDMI_HOT_OUT") (class "Default")
      (node (ref "IC2") (pin "F8") (pinfunction "HPD_OUT_AUX_HPD_F8") (pintype "passive"))
      (node (ref "R30") (pin "2") (pinfunction "2_2") (pintype "passive"))
    )
    (net (code "36") (name "/HDMI_SCL") (class "Default")
      (node (ref "IC2") (pin "H2") (pinfunction "HDMI_DDC_SCL_H2") (pintype "passive"))
      (node (ref "R47") (pin "2") (pinfunction "2_2") (pintype "passive"))
    )
    (net (code "37") (name "/HDMI_SDA") (class "Default")
      (node (ref "IC2") (pin "G2") (pinfunction "HDMI_DDC_SDA_G2") (pintype "passive"))
      (node (ref "R48") (pin "2") (pinfunction "2_2") (pintype "passive"))
    )
    (net (code "38") (name "/HDMI_TD0_N") (class "Default")
      (node (ref "IC2") (pin "A6") (pinfunction "HDMI_RX0N_A6") (pintype "passive"))
    )
    (net (code "39") (name "/HDMI_TD0_P") (class "Default")
      (node (ref "IC2") (pin "A5") (pinfunction "HDMI_RX0P_A5") (pintype "passive"))
    )
    (net (code "40") (name "/HDMI_TD1_N") (class "Default")
      (node (ref "IC2") (pin "A4") (pinfunction "HDMI_RX1N_A4") (pintype "passive"))
    )
    (net (code "41") (name "/HDMI_TD1_P") (class "Default")
      (node (ref "IC2") (pin "A3") (pinfunction "HDMI_RX1P_A3") (pintype "passive"))
    )
    (net (code "42") (name "/HDMI_TD2_N") (class "Default")
      (node (ref "IC2") (pin "A2") (pinfunction "HDMI_RX2N_A2") (pintype "passive"))
    )
    (net (code "43") (name "/HDMI_TD2_P") (class "Default")
      (node (ref "IC2") (pin "A1") (pinfunction "HDMI_RX2P_A1") (pintype "passive"))
    )
    (net (code "44") (name "/IRQ") (class "Default")
      (node (ref "IC2") (pin "E9") (pinfunction "IRQ_E9") (pintype "passive"))
      (node (ref "R38") (pin "2") (pinfunction "2_2") (pintype "passive"))
      (node (ref "R39") (pin "1") (pinfunction "1_1") (pintype "passive"))
    )
    (net (code "45") (name "/PWR_CTRL") (class "Default")
      (node (ref "IC2") (pin "D1") (pinfunction "PWR_CTRL_D1") (pintype "passive"))
      (node (ref "R24") (pin "1") (pinfunction "1_1") (pintype "passive"))
    )
    (net (code "46") (name "/RESET_STDP") (class "Default")
      (node (ref "IC2") (pin "G8") (pinfunction "RESETn_G8") (pintype "passive"))
      (node (ref "R147") (pin "2") (pinfunction "2_2") (pintype "passive"))
      (node (ref "R28") (pin "2") (pinfunction "2_2") (pintype "passive"))
    )
    (net (code "47") (name "/RXD") (class "Default")
      (node (ref "IC2") (pin "C9") (pinfunction "UART_RX_C9") (pintype "passive"))
      (node (ref "J3") (pin "1") (pinfunction "1_1") (pintype "passive"))
      (node (ref "R23") (pin "1") (pinfunction "1_1") (pintype "passive"))
    )
    (net (code "48") (name "/RX_REXT") (class "Default")
      (node (ref "IC2") (pin "B6") (pinfunction "CPHY_RX_REXT_B6") (pintype "passive"))
      (node (ref "R145") (pin "1") (pinfunction "1_1") (pintype "passive"))
    )
    (net (code "49") (name "/SPDIF") (class "Default")
      (node (ref "IC2") (pin "F2") (pinfunction "SPDIF_F2") (pintype "passive"))
      (node (ref "R49") (pin "2") (pinfunction "2_2") (pintype "passive"))
      (node (ref "R50") (pin "1") (pinfunction "1_1") (pintype "passive"))
    )
    (net (code "50") (name "/TCLK") (class "Default")
      (node (ref "C129") (pin "2") (pinfunction "2_2") (pintype "passive"))
      (node (ref "IC2") (pin "H9") (pinfunction "TCLK_H9") (pintype "passive"))
      (node (ref "Y3") (pin "3") (pinfunction "3_3") (pintype "passive"))
    )
    (net (code "51") (name "/TEST_MISN") (class "Default")
      (node (ref "IC2") (pin "B8") (pinfunction "TEST_MISN_B8") (pintype "passive"))
      (node (ref "R42") (pin "1") (pinfunction "1_1") (pintype "passive"))
    )
    (net (code "52") (name "/TXD") (class "Default")
      (node (ref "IC2") (pin "D9") (pinfunction "UART_TX_D9") (pintype "passive"))
      (node (ref "J3") (pin "2") (pinfunction "2_2") (pintype "passive"))
      (node (ref "R36") (pin "2") (pinfunction "2_2") (pintype "passive"))
      (node (ref "R37") (pin "1") (pinfunction "1_1") (pintype "passive"))
    )
    (net (code "53") (name "/TX_REXT") (class "Default")
      (node (ref "IC2") (pin "H3") (pinfunction "TX_REXT_H3") (pintype "passive"))
      (node (ref "R146") (pin "1") (pinfunction "1_1") (pintype "passive"))
    )
    (net (code "54") (name "/XAUX_N") (class "Default")
      (node (ref "C115") (pin "2") (pinfunction "2_2") (pintype "passive"))
      (node (ref "IC2") (pin "H1") (pinfunction "DPTX_AUXN_H1") (pintype "passive"))
    )
    (net (code "55") (name "/XAUX_P") (class "Default")
      (node (ref "C116") (pin "2") (pinfunction "2_2") (pintype "passive"))
      (node (ref "IC2") (pin "J1") (pinfunction "DPTX_AUXP_J1") (pintype "passive"))
    )
    (net (code "56") (name "/XDP0_N") (class "Default")
      (node (ref "C124") (pin "2") (pinfunction "2_2") (pintype "passive"))
      (node (ref "IC2") (pin "J8") (pinfunction "DPTX_L0N_HDMI_TX2N_J8") (pintype "passive"))
    )
    (net (code "57") (name "/XDP0_P") (class "Default")
      (node (ref "C125") (pin "2") (pinfunction "2_2") (pintype "passive"))
      (node (ref "IC2") (pin "J9") (pinfunction "DPTX_L0P_HDMI_TX2P_J9") (pintype "passive"))
    )
    (net (code "58") (name "/XDP1_N") (class "Default")
      (node (ref "C122") (pin "2") (pinfunction "2_2") (pintype "passive"))
      (node (ref "IC2") (pin "J6") (pinfunction "DPTX_L1N_HDMI_TX1N_J6") (pintype "passive"))
    )
    (net (code "59") (name "/XDP1_P") (class "Default")
      (node (ref "C123") (pin "2") (pinfunction "2_2") (pintype "passive"))
      (node (ref "IC2") (pin "J7") (pinfunction "DPTX_L1P_HDMI_TX1P_J7") (pintype "passive"))
    )
    (net (code "60") (name "/XDP2_N") (class "Default")
      (node (ref "C120") (pin "2") (pinfunction "2_2") (pintype "passive"))
      (node (ref "IC2") (pin "J4") (pinfunction "DPTX_L2N_HDMI_TX0N_J4") (pintype "passive"))
    )
    (net (code "61") (name "/XDP2_P") (class "Default")
      (node (ref "C121") (pin "2") (pinfunction "2_2") (pintype "passive"))
      (node (ref "IC2") (pin "J5") (pinfunction "DPTX_L2P_HDMI_TX0P_J5") (pintype "passive"))
    )
    (net (code "62") (name "/XDP3_N") (class "Default")
      (node (ref "C118") (pin "2") (pinfunction "2_2") (pintype "passive"))
      (node (ref "IC2") (pin "J2") (pinfunction "DPTX_L3N_HDMI_TXCKN_J2") (pintype "passive"))
    )
    (net (code "63") (name "/XDP3_P") (class "Default")
      (node (ref "C119") (pin "2") (pinfunction "2_2") (pintype "passive"))
      (node (ref "IC2") (pin "J3") (pinfunction "DPTX_L3P_HDMI_TXCKP_J3") (pintype "passive"))
    )
    (net (code "64") (name "/XTAL") (class "Default")
      (node (ref "C128") (pin "2") (pinfunction "2_2") (pintype "passive"))
      (node (ref "IC2") (pin "G9") (pinfunction "XTAL_G9") (pintype "passive"))
      (node (ref "Y3") (pin "1") (pinfunction "1_1") (pintype "passive"))
    )
    (net (code "65") (name "/nEXTRST") (class "Default")
      (node (ref "R28") (pin "1") (pinfunction "1_1") (pintype "passive"))
    )
    (net (code "69") (name "GND") (class "Default")
      (node (ref "C100") (pin "2") (pinfunction "2_2") (pintype "passive"))
      (node (ref "C101") (pin "2") (pinfunction "2_2") (pintype "passive"))
      (node (ref "C102") (pin "2") (pinfunction "2_2") (pintype "passive"))
      (node (ref "C103") (pin "2") (pinfunction "2_2") (pintype "passive"))
      (node (ref "C104") (pin "2") (pinfunction "2_2") (pintype "passive"))
      (node (ref "C105") (pin "2") (pinfunction "2_2") (pintype "passive"))
      (node (ref "C106") (pin "2") (pinfunction "2_2") (pintype "passive"))
      (node (ref "C107") (pin "2") (pinfunction "2_2") (pintype "passive"))
      (node (ref "C108") (pin "2") (pinfunction "2_2") (pintype "passive"))
      (node (ref "C109") (pin "2") (pinfunction "2_2") (pintype "passive"))
      (node (ref "C110") (pin "2") (pinfunction "2_2") (pintype "passive"))
      (node (ref "C111") (pin "2") (pinfunction "2_2") (pintype "passive"))
      (node (ref "C112") (pin "2") (pinfunction "2_2") (pintype "passive"))
      (node (ref "C113") (pin "2") (pinfunction "2_2") (pintype "passive"))
      (node (ref "C114") (pin "2") (pinfunction "2_2") (pintype "passive"))
      (node (ref "C117") (pin "1") (pinfunction "1_1") (pintype "passive"))
      (node (ref "C92") (pin "2") (pinfunction "2_2") (pintype "passive"))
      (node (ref "C93") (pin "2") (pinfunction "2_2") (pintype "passive"))
      (node (ref "C94") (pin "2") (pinfunction "2_2") (pintype "passive"))
      (node (ref "C95") (pin "2") (pinfunction "2_2") (pintype "passive"))
      (node (ref "C96") (pin "2") (pinfunction "2_2") (pintype "passive"))
      (node (ref "C97") (pin "2") (pinfunction "2_2") (pintype "passive"))
      (node (ref "C98") (pin "2") (pinfunction "2_2") (pintype "passive"))
      (node (ref "C99") (pin "2") (pinfunction "2_2") (pintype "passive"))
      (node (ref "IC12") (pin "4") (pinfunction "VSS_4") (pintype "passive"))
      (node (ref "IC2") (pin "C3") (pinfunction "GND_C3") (pintype "passive"))
      (node (ref "IC2") (pin "C4") (pinfunction "GND_C4") (pintype "passive"))
      (node (ref "IC2") (pin "D4") (pinfunction "GND_D4") (pintype "passive"))
      (node (ref "IC2") (pin "D5") (pinfunction "GND_D5") (pintype "passive"))
      (node (ref "IC2") (pin "D6") (pinfunction "GND_D6") (pintype "passive"))
      (node (ref "IC2") (pin "E4") (pinfunction "GND_E4") (pintype "passive"))
      (node (ref "IC2") (pin "E5") (pinfunction "GND_E5") (pintype "passive"))
      (node (ref "IC2") (pin "E6") (pinfunction "GND_E6") (pintype "passive"))
      (node (ref "IC2") (pin "E8") (pinfunction "GND_E8") (pintype "passive"))
      (node (ref "IC2") (pin "F4") (pinfunction "GND_F4") (pintype "passive"))
      (node (ref "IC2") (pin "F5") (pinfunction "GND_F5") (pintype "passive"))
      (node (ref "IC2") (pin "F6") (pinfunction "GND_F6") (pintype "passive"))
      (node (ref "IC2") (pin "F7") (pinfunction "GND_F7") (pintype "passive"))
      (node (ref "IC2") (pin "G4") (pinfunction "GND_G4") (pintype "passive"))
      (node (ref "IC2") (pin "G5") (pinfunction "GND_G5") (pintype "passive"))
      (node (ref "IC2") (pin "G7") (pinfunction "GND_G7") (pintype "passive"))
      (node (ref "J3") (pin "3") (pinfunction "3_3") (pintype "passive"))
      (node (ref "Q1") (pin "2") (pinfunction "S_2") (pintype "passive"))
      (node (ref "R24") (pin "2") (pinfunction "2_2") (pintype "passive"))
      (node (ref "R26") (pin "2") (pinfunction "2_2") (pintype "passive"))
      (node (ref "R32") (pin "2") (pinfunction "2_2") (pintype "passive"))
      (node (ref "R33") (pin "2") (pinfunction "2_2") (pintype "passive"))
      (node (ref "R34") (pin "1") (pinfunction "1_1") (pintype "passive"))
      (node (ref "R35") (pin "1") (pinfunction "1_1") (pintype "passive"))
      (node (ref "R37") (pin "2") (pinfunction "2_2") (pintype "passive"))
      (node (ref "R39") (pin "2") (pinfunction "2_2") (pintype "passive"))
      (node (ref "R41") (pin "2") (pinfunction "2_2") (pintype "passive"))
      (node (ref "R42") (pin "2") (pinfunction "2_2") (pintype "passive"))
      (node (ref "R43") (pin "1") (pinfunction "1_1") (pintype "passive"))
      (node (ref "R46") (pin "2") (pinfunction "2_2") (pintype "passive"))
      (node (ref "R50") (pin "2") (pinfunction "2_2") (pintype "passive"))
      (node (ref "R52") (pin "2") (pinfunction "2_2") (pintype "passive"))
    )
    (net (code "70") (name "Net-(D3-Cathode)") (class "Default")
      (node (ref "D3") (pin "1") (pinfunction "Cathode_1") (pintype "passive"))
      (node (ref "R53") (pin "1") (pinfunction "1_1") (pintype "passive"))
    )
    (net (code "71") (name "Net-(IC12-HOLD#)") (class "Default")
      (node (ref "IC12") (pin "7") (pinfunction "HOLD#_7") (pintype "passive"))
      (node (ref "R27") (pin "1") (pinfunction "1_1") (pintype "passive"))
    )
    (net (code "72") (name "Net-(IC12-WP#)") (class "Default")
      (node (ref "IC12") (pin "3") (pinfunction "WP#_3") (pintype "passive"))
      (node (ref "R143") (pin "2") (pinfunction "2_2") (pintype "passive"))
    )
    (net (code "73") (name "Net-(Q1-G)") (class "Default")
      (node (ref "Q1") (pin "1") (pinfunction "G_1") (pintype "passive"))
      (node (ref "R30") (pin "1") (pinfunction "1_1") (pintype "passive"))
      (node (ref "R32") (pin "1") (pinfunction "1_1") (pintype "passive"))
    )
    (net (code "74") (name "unconnected-(IC2-NC-PadA9)") (class "Default")
      (node (ref "IC2") (pin "A9") (pinfunction "NC_A9") (pintype "passive"))
    )
    (net (code "75") (name "unconnected-(IC2-NC-PadB9)") (class "Default")
      (node (ref "IC2") (pin "B9") (pinfunction "NC_B9") (pintype "passive"))
    )
  )
)
